# Power_Supplies.net
KiCad netlist of a schematic drawn in Altium Designer
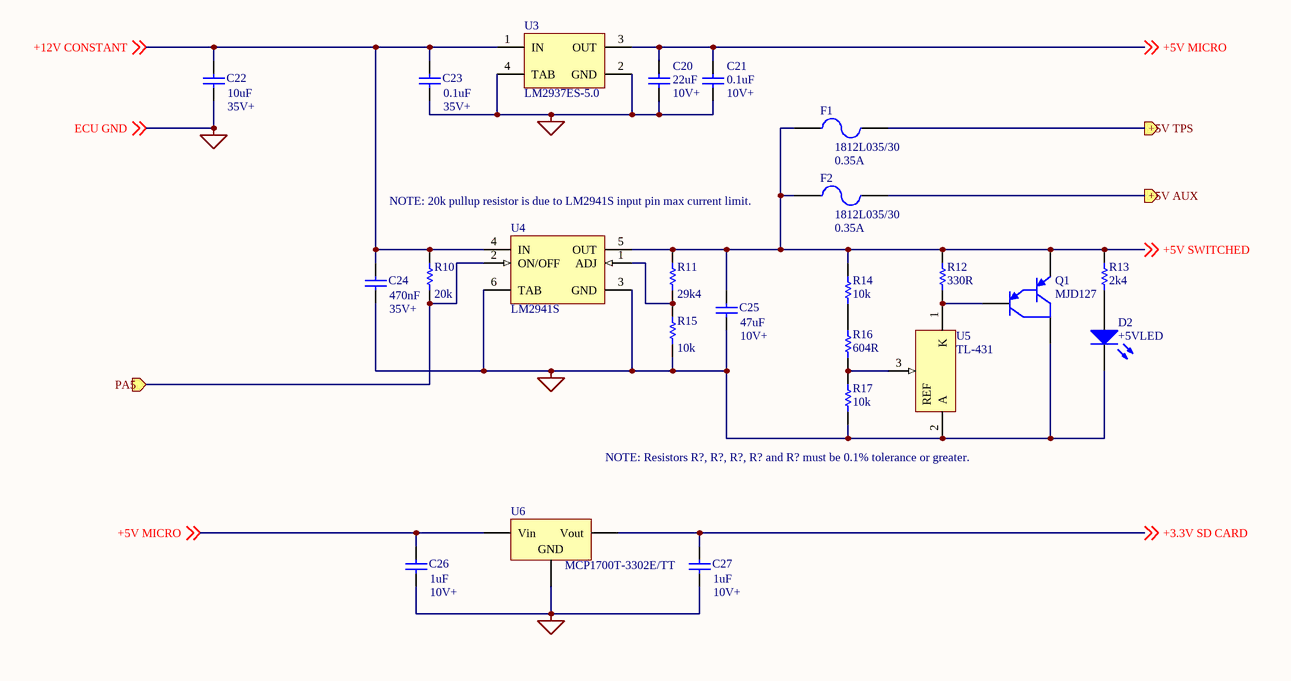
[diagram p0: Power Supplies.SchDoc]

(export (version "E")
  (design (tool "Eeschema 10.0.6"))
  (components
    (comp (ref "C20")
      (value "22uF")
      (footprint "RAD-0.3")
      (description "Capacitor")
      (fields (field (name "PUBLISHER") "Altium Limited"))
      (libsource (lib "Miscellaneous Devices") (part "Cap"))
    )
    (comp (ref "C21")
      (value "0.1uF")
      (footprint "RAD-0.3")
      (description "Capacitor")
      (fields (field (name "PUBLISHER") "Altium Limited"))
      (libsource (lib "Miscellaneous Devices") (part "Cap"))
    )
    (comp (ref "C22")
      (value "10uF")
      (footprint "RAD-0.3")
      (description "Capacitor")
      (fields (field (name "PUBLISHER") "Altium Limited"))
      (libsource (lib "Miscellaneous Devices") (part "Cap"))
    )
    (comp (ref "C23")
      (value "0.1uF")
      (footprint "RAD-0.3")
      (description "Capacitor")
      (fields (field (name "PUBLISHER") "Altium Limited"))
      (libsource (lib "Miscellaneous Devices") (part "Cap"))
    )
    (comp (ref "C24")
      (value "470nF")
      (footprint "RAD-0.3")
      (description "Capacitor")
      (fields (field (name "PUBLISHER") "Altium Limited"))
      (libsource (lib "Miscellaneous Devices") (part "Cap"))
    )
    (comp (ref "C25")
      (value "47uF")
      (footprint "RAD-0.3")
      (description "Capacitor")
      (fields (field (name "PUBLISHER") "Altium Limited"))
      (libsource (lib "Miscellaneous Devices") (part "Cap"))
    )
    (comp (ref "C26")
      (value "1uF")
      (footprint "RAD-0.3")
      (description "Capacitor")
      (fields (field (name "PUBLISHER") "Altium Limited"))
      (libsource (lib "Miscellaneous Devices") (part "Cap"))
    )
    (comp (ref "C27")
      (value "1uF")
      (footprint "RAD-0.3")
      (description "Capacitor")
      (fields (field (name "PUBLISHER") "Altium Limited"))
      (libsource (lib "Miscellaneous Devices") (part "Cap"))
    )
    (comp (ref "D2")
      (value "+5VLED")
      (footprint "LED-0")
      (description "Typical INFRARED GaAs LED")
      (fields (field (name "PUBLISHER") "Altium Limited"))
      (libsource (lib "Miscellaneous Devices") (part "LED0"))
    )
    (comp (ref "F1")
      (value "1812L035/30")
      (footprint "PIN-W2/E2.8")
      (description "Fuse")
      (fields (field (name "PUBLISHER") "Altium Limited"))
      (libsource (lib "Miscellaneous Devices") (part "Fuse 2"))
    )
    (comp (ref "F2")
      (value "1812L035/30")
      (footprint "PIN-W2/E2.8")
      (description "Fuse")
      (fields (field (name "PUBLISHER") "Altium Limited"))
      (libsource (lib "Miscellaneous Devices") (part "Fuse 2"))
    )
    (comp (ref "Q1")
      (value "MJD127")
      (footprint "E3")
      (description "PNP Darlington Bipolar Transistor")
      (fields (field (name "PUBLISHER") "Altium Limited"))
      (libsource (lib "Miscellaneous Devices") (part "PNP1"))
    )
    (comp (ref "R10")
      (value "20k")
      (footprint "AXIAL-0.3")
      (description "Resistor")
      (fields (field (name "PUBLISHER") "Altium Limited"))
      (libsource (lib "Miscellaneous Devices") (part "Res1"))
    )
    (comp (ref "R11")
      (value "29k4")
      (footprint "AXIAL-0.3")
      (description "Resistor")
      (fields (field (name "PUBLISHER") "Altium Limited"))
      (libsource (lib "Miscellaneous Devices") (part "Res1"))
    )
    (comp (ref "R12")
      (value "330R")
      (footprint "AXIAL-0.3")
      (description "Resistor")
      (fields (field (name "PUBLISHER") "Altium Limited"))
      (libsource (lib "Miscellaneous Devices") (part "Res1"))
    )
    (comp (ref "R13")
      (value "2k4")
      (footprint "AXIAL-0.3")
      (description "Resistor")
      (fields (field (name "PUBLISHER") "Altium Limited"))
      (libsource (lib "Miscellaneous Devices") (part "Res1"))
    )
    (comp (ref "R14")
      (value "10k")
      (footprint "AXIAL-0.3")
      (description "Resistor")
      (fields (field (name "PUBLISHER") "Altium Limited"))
      (libsource (lib "Miscellaneous Devices") (part "Res1"))
    )
    (comp (ref "R15")
      (value "10k")
      (footprint "AXIAL-0.3")
      (description "Resistor")
      (fields (field (name "PUBLISHER") "Altium Limited"))
      (libsource (lib "Miscellaneous Devices") (part "Res1"))
    )
    (comp (ref "R16")
      (value "604R")
      (footprint "AXIAL-0.3")
      (description "Resistor")
      (fields (field (name "PUBLISHER") "Altium Limited"))
      (libsource (lib "Miscellaneous Devices") (part "Res1"))
    )
    (comp (ref "R17")
      (value "10k")
      (footprint "AXIAL-0.3")
      (description "Resistor")
      (fields (field (name "PUBLISHER") "Altium Limited"))
      (libsource (lib "Miscellaneous Devices") (part "Res1"))
    )
    (comp (ref "U3")
      (value "LM2937ES-5.0")
      (footprint "TS3B_N")
      (description "500 mA Low Dropout Regulator, 3-pin TO-263")
      (fields
        (field (name "MANUFACTURER") "National Semiconductor")
        (field (name "PUBLISHER") "Altium Limited")
      )
      (libsource (lib "NSC LDO") (part "LM2937ES-5.0"))
    )
    (comp (ref "U4")
      (value "LM2941S")
      (footprint "TS5B_N")
      (description "1A Low Dropout Adjustable Regulator, 5-pin TO-263")
      (fields
        (field (name "MANUFACTURER") "National Semiconductor")
        (field (name "PUBLISHER") "Altium Limited")
      )
      (libsource (lib "NSC LDO") (part "LM2941S"))
    )
    (comp (ref "U5") (value "TL-431") (libsource (lib "PM-REF-431-SIL3") (part "PM-REF-431-SIL3")))
    (comp (ref "U6")
      (value "MCP1700T-3302E/TT")
      (footprint "SOT-23-NB3_M")
      (description "Voltage Regulator")
      (fields (field (name "PUBLISHER") "Altium Limited"))
      (libsource (lib "Miscellaneous Devices") (part "Volt Reg"))
    )
  )
  (nets
    (net (code "1") (name "+3.3V SD CARD") (class "Default")
      (node (ref "C27") (pin "2") (pinfunction "2_2") (pintype "passive"))
      (node (ref "U6") (pin "2") (pinfunction "Vout_2") (pintype "passive"))
    )
    (net (code "2") (name "+5V MICRO") (class "Default")
      (node (ref "C20") (pin "2") (pinfunction "2_2") (pintype "passive"))
      (node (ref "C21") (pin "2") (pinfunction "2_2") (pintype "passive"))
      (node (ref "C26") (pin "2") (pinfunction "2_2") (pintype "passive"))
      (node (ref "U3") (pin "3") (pinfunction "OUT_3") (pintype "power_in"))
      (node (ref "U6") (pin "3") (pinfunction "Vin_3") (pintype "passive"))
    )
    (net (code "3") (name "+5V SWITCHED") (class "Default")
      (node (ref "C25") (pin "2") (pinfunction "2_2") (pintype "passive"))
      (node (ref "F1") (pin "1") (pinfunction "1_1") (pintype "passive"))
      (node (ref "F2") (pin "1") (pinfunction "1_1") (pintype "passive"))
      (node (ref "Q1") (pin "1") (pinfunction "E_1") (pintype "passive"))
      (node (ref "R11") (pin "2") (pinfunction "2_2") (pintype "passive"))
      (node (ref "R12") (pin "2") (pinfunction "2_2") (pintype "passive"))
      (node (ref "R13") (pin "2") (pinfunction "2_2") (pintype "passive"))
      (node (ref "R14") (pin "2") (pinfunction "2_2") (pintype "passive"))
      (node (ref "U4") (pin "5") (pinfunction "OUT_5") (pintype "power_in"))
    )
    (net (code "4") (name "+12V CONSTANT") (class "Default")
      (node (ref "C22") (pin "2") (pinfunction "2_2") (pintype "passive"))
      (node (ref "C23") (pin "2") (pinfunction "2_2") (pintype "passive"))
      (node (ref "C24") (pin "2") (pinfunction "2_2") (pintype "passive"))
      (node (ref "R10") (pin "2") (pinfunction "2_2") (pintype "passive"))
      (node (ref "U3") (pin "1") (pinfunction "IN_1") (pintype "power_in"))
      (node (ref "U4") (pin "4") (pinfunction "IN_4") (pintype "power_in"))
    )
    (net (code "5") (name "/+5V AUX") (class "Default")
      (node (ref "F2") (pin "2") (pinfunction "2_2") (pintype "passive"))
    )
    (net (code "6") (name "/+5V TPS") (class "Default")
      (node (ref "F1") (pin "2") (pinfunction "2_2") (pintype "passive"))
    )
    (net (code "7") (name "/PA5") (class "Default")
      (node (ref "R10") (pin "1") (pinfunction "1_1") (pintype "passive"))
      (node (ref "U4") (pin "2") (pinfunction "ON/OFF_2") (pintype "input"))
    )
    (net (code "8") (name "<NO NET>") (class "Default")
      (node (ref "C20") (pin "1") (pinfunction "1_1") (pintype "passive"))
      (node (ref "C21") (pin "1") (pinfunction "1_1") (pintype "passive"))
      (node (ref "C22") (pin "1") (pinfunction "1_1") (pintype "passive"))
      (node (ref "C23") (pin "1") (pinfunction "1_1") (pintype "passive"))
      (node (ref "C24") (pin "1") (pinfunction "1_1") (pintype "passive"))
      (node (ref "C25") (pin "1") (pinfunction "1_1") (pintype "passive"))
      (node (ref "C26") (pin "1") (pinfunction "1_1") (pintype "passive"))
      (node (ref "C27") (pin "1") (pinfunction "1_1") (pintype "passive"))
      (node (ref "D2") (pin "2") (pinfunction "K_2") (pintype "passive"))
      (node (ref "Q1") (pin "3") (pinfunction "C_3") (pintype "passive"))
      (node (ref "R15") (pin "1") (pinfunction "1_1") (pintype "passive"))
      (node (ref "R17") (pin "1") (pinfunction "1_1") (pintype "passive"))
      (node (ref "U3") (pin "2") (pinfunction "GND_2") (pintype "power_in"))
      (node (ref "U3") (pin "4") (pinfunction "TAB_4") (pintype "power_in"))
      (node (ref "U4") (pin "3") (pinfunction "GND_3") (pintype "power_in"))
      (node (ref "U4") (pin "6") (pinfunction "TAB_6") (pintype "power_in"))
      (node (ref "U5") (pin "2") (pinfunction "A_2") (pintype "passive"))
      (node (ref "U6") (pin "1") (pintype "passive"))
    )
    (net (code "9") (name "Net-(D2-A)") (class "Default")
      (node (ref "D2") (pin "1") (pinfunction "A_1") (pintype "passive"))
      (node (ref "R13") (pin "1") (pinfunction "1_1") (pintype "passive"))
    )
    (net (code "10") (name "Net-(Q1-B)") (class "Default")
      (node (ref "Q1") (pin "2") (pinfunction "B_2") (pintype "passive"))
      (node (ref "R12") (pin "1") (pinfunction "1_1") (pintype "passive"))
      (node (ref "U5") (pin "1") (pinfunction "K_1") (pintype "passive"))
    )
    (net (code "11") (name "Net-(R14-Pad1)") (class "Default")
      (node (ref "R14") (pin "1") (pinfunction "1_1") (pintype "passive"))
      (node (ref "R16") (pin "2") (pinfunction "2_2") (pintype "passive"))
    )
    (net (code "12") (name "Net-(U4-ADJ)") (class "Default")
      (node (ref "R11") (pin "1") (pinfunction "1_1") (pintype "passive"))
      (node (ref "R15") (pin "2") (pinfunction "2_2") (pintype "passive"))
      (node (ref "U4") (pin "1") (pinfunction "ADJ_1") (pintype "input"))
    )
    (net (code "13") (name "Net-(U5-REF)") (class "Default")
      (node (ref "R16") (pin "1") (pinfunction "1_1") (pintype "passive"))
      (node (ref "R17") (pin "2") (pinfunction "2_2") (pintype "passive"))
      (node (ref "U5") (pin "3") (pinfunction "REF_3") (pintype "input"))
    )
  )
)
